# plus2_sram.net
KiCad netlist of a schematic drawn in EAGLE
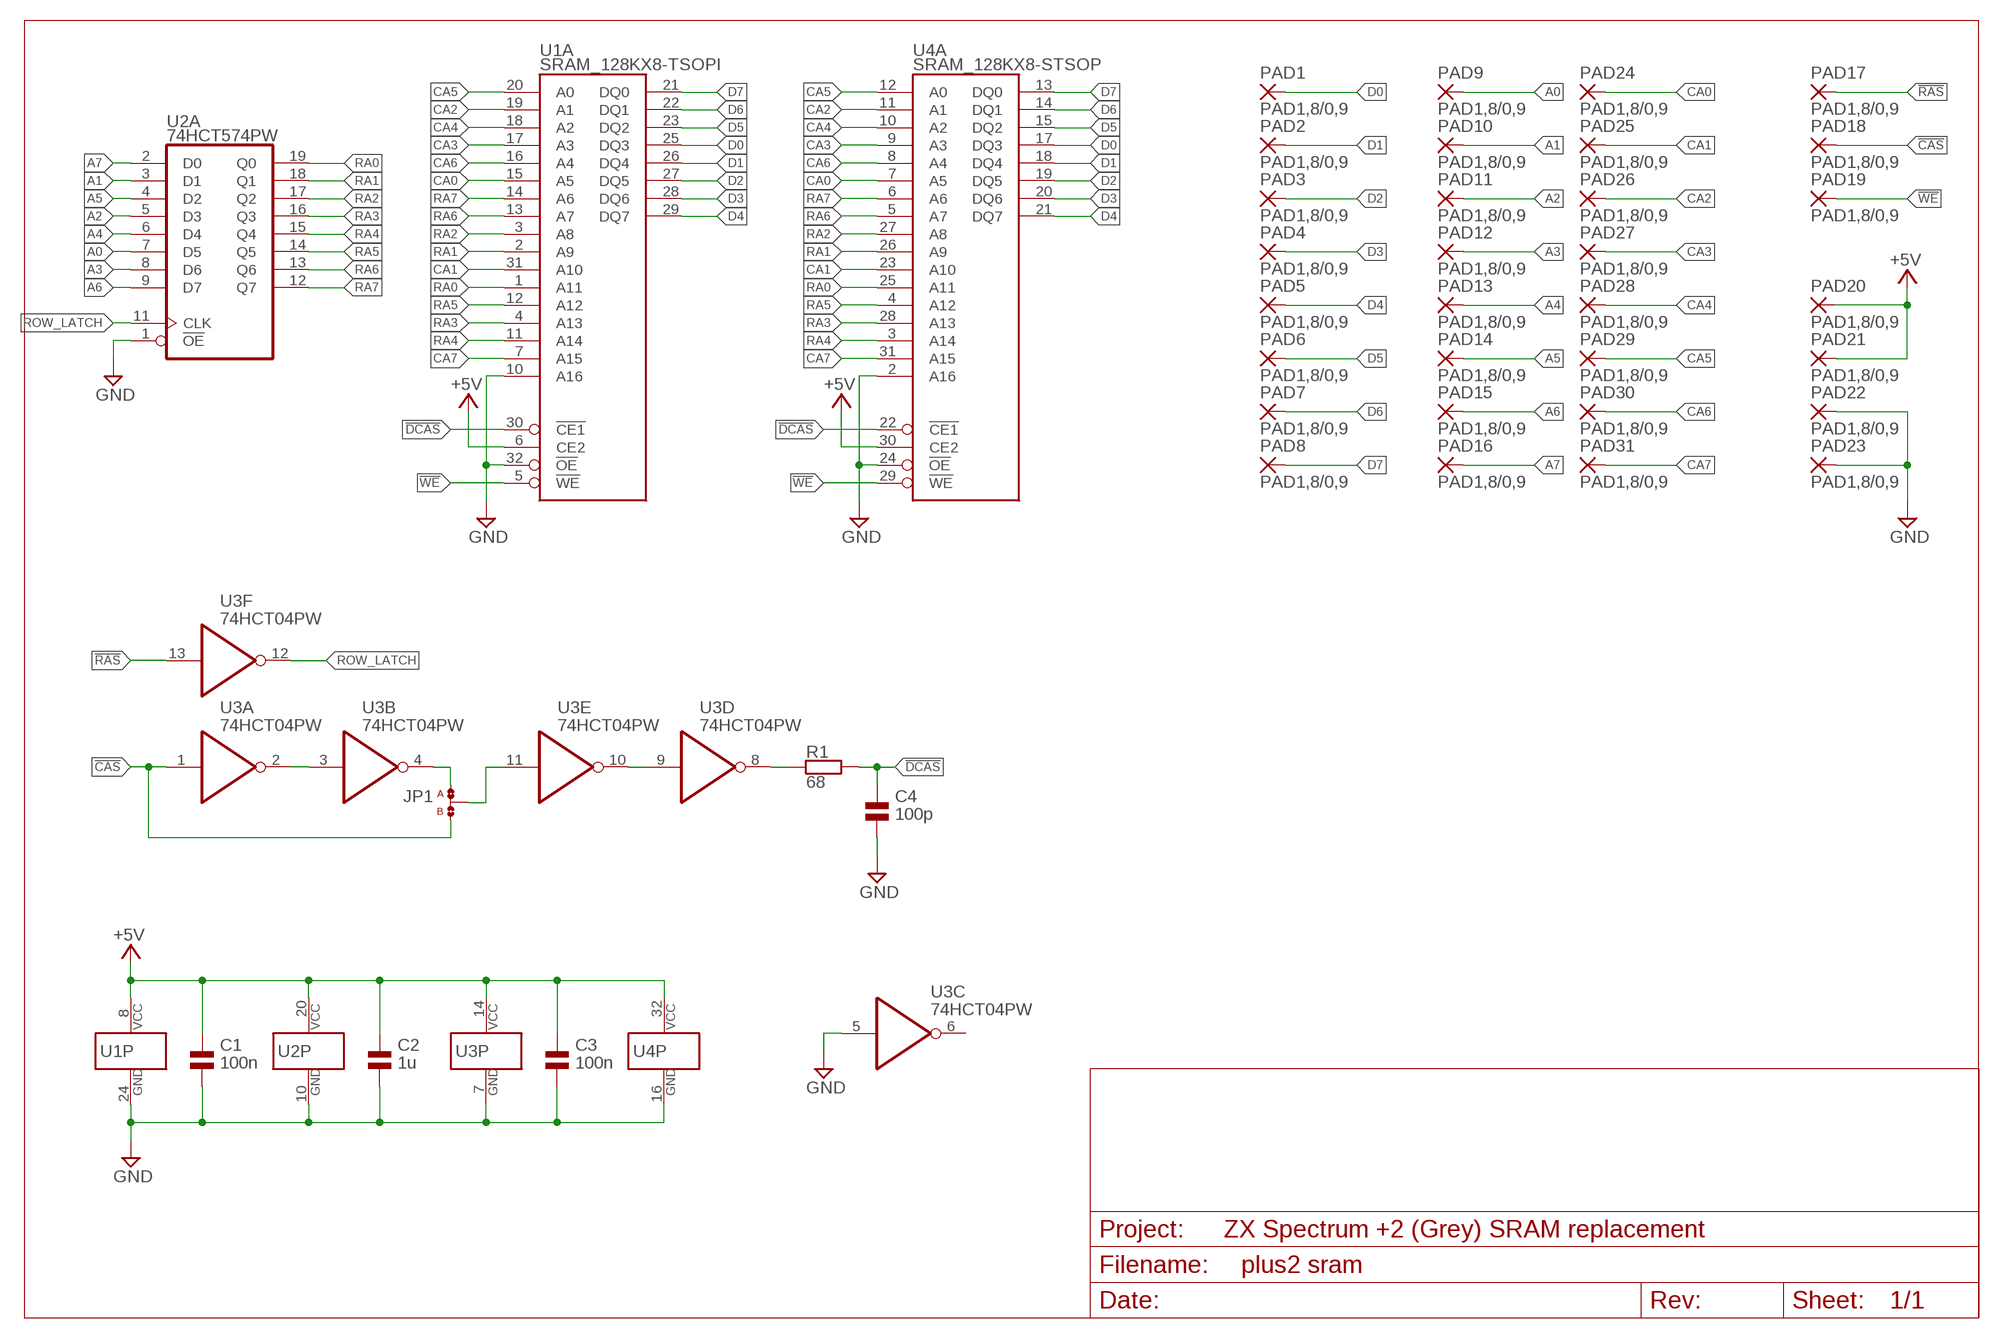
[diagram p0: schematic, sheet 1]

(export (version "E")
  (design (tool "Eeschema 10.0.6"))
  (components
    (comp (ref "C1")
      (value "100n")
      (footprint "eagle-import:0603")
      (libsource (lib "eagle-import") (part "CAP_NPOL0603-"))
    )
    (comp (ref "C2")
      (value "1u")
      (footprint "eagle-import:0603")
      (libsource (lib "eagle-import") (part "CAP_NPOL0603-"))
    )
    (comp (ref "C3")
      (value "100n")
      (footprint "eagle-import:0603")
      (libsource (lib "eagle-import") (part "CAP_NPOL0603-"))
    )
    (comp (ref "C4")
      (value "100p")
      (footprint "eagle-import:0603")
      (libsource (lib "eagle-import") (part "CAP_NPOL0603-"))
    )
    (comp (ref "JP1")
      (value "JMP-SMD-3W0805")
      (footprint "eagle-import:SJ-3P-0805")
      (libsource (lib "eagle-import") (part "JMP-SMD-3W0805"))
    )
    (comp (ref "PAD1")
      (value "PAD1,8/0,9")
      (footprint "eagle-import:1,8_0,9")
      (libsource (lib "eagle-import") (part "PAD1,8/0,9"))
    )
    (comp (ref "PAD2")
      (value "PAD1,8/0,9")
      (footprint "eagle-import:1,8_0,9")
      (libsource (lib "eagle-import") (part "PAD1,8/0,9"))
    )
    (comp (ref "PAD3")
      (value "PAD1,8/0,9")
      (footprint "eagle-import:1,8_0,9")
      (libsource (lib "eagle-import") (part "PAD1,8/0,9"))
    )
    (comp (ref "PAD4")
      (value "PAD1,8/0,9")
      (footprint "eagle-import:1,8_0,9")
      (libsource (lib "eagle-import") (part "PAD1,8/0,9"))
    )
    (comp (ref "PAD5")
      (value "PAD1,8/0,9")
      (footprint "eagle-import:1,8_0,9")
      (libsource (lib "eagle-import") (part "PAD1,8/0,9"))
    )
    (comp (ref "PAD6")
      (value "PAD1,8/0,9")
      (footprint "eagle-import:1,8_0,9")
      (libsource (lib "eagle-import") (part "PAD1,8/0,9"))
    )
    (comp (ref "PAD7")
      (value "PAD1,8/0,9")
      (footprint "eagle-import:1,8_0,9")
      (libsource (lib "eagle-import") (part "PAD1,8/0,9"))
    )
    (comp (ref "PAD8")
      (value "PAD1,8/0,9")
      (footprint "eagle-import:1,8_0,9")
      (libsource (lib "eagle-import") (part "PAD1,8/0,9"))
    )
    (comp (ref "PAD9")
      (value "PAD1,8/0,9")
      (footprint "eagle-import:1,8_0,9")
      (libsource (lib "eagle-import") (part "PAD1,8/0,9"))
    )
    (comp (ref "PAD10")
      (value "PAD1,8/0,9")
      (footprint "eagle-import:1,8_0,9")
      (libsource (lib "eagle-import") (part "PAD1,8/0,9"))
    )
    (comp (ref "PAD11")
      (value "PAD1,8/0,9")
      (footprint "eagle-import:1,8_0,9")
      (libsource (lib "eagle-import") (part "PAD1,8/0,9"))
    )
    (comp (ref "PAD12")
      (value "PAD1,8/0,9")
      (footprint "eagle-import:1,8_0,9")
      (libsource (lib "eagle-import") (part "PAD1,8/0,9"))
    )
    (comp (ref "PAD13")
      (value "PAD1,8/0,9")
      (footprint "eagle-import:1,8_0,9")
      (libsource (lib "eagle-import") (part "PAD1,8/0,9"))
    )
    (comp (ref "PAD14")
      (value "PAD1,8/0,9")
      (footprint "eagle-import:1,8_0,9")
      (libsource (lib "eagle-import") (part "PAD1,8/0,9"))
    )
    (comp (ref "PAD15")
      (value "PAD1,8/0,9")
      (footprint "eagle-import:1,8_0,9")
      (libsource (lib "eagle-import") (part "PAD1,8/0,9"))
    )
    (comp (ref "PAD16")
      (value "PAD1,8/0,9")
      (footprint "eagle-import:1,8_0,9")
      (libsource (lib "eagle-import") (part "PAD1,8/0,9"))
    )
    (comp (ref "PAD17")
      (value "PAD1,8/0,9")
      (footprint "eagle-import:1,8_0,9")
      (libsource (lib "eagle-import") (part "PAD1,8/0,9"))
    )
    (comp (ref "PAD18")
      (value "PAD1,8/0,9")
      (footprint "eagle-import:1,8_0,9")
      (libsource (lib "eagle-import") (part "PAD1,8/0,9"))
    )
    (comp (ref "PAD19")
      (value "PAD1,8/0,9")
      (footprint "eagle-import:1,8_0,9")
      (libsource (lib "eagle-import") (part "PAD1,8/0,9"))
    )
    (comp (ref "PAD20")
      (value "PAD1,8/0,9")
      (footprint "eagle-import:1,8_0,9")
      (libsource (lib "eagle-import") (part "PAD1,8/0,9"))
    )
    (comp (ref "PAD21")
      (value "PAD1,8/0,9")
      (footprint "eagle-import:1,8_0,9")
      (libsource (lib "eagle-import") (part "PAD1,8/0,9"))
    )
    (comp (ref "PAD22")
      (value "PAD1,8/0,9")
      (footprint "eagle-import:1,8_0,9")
      (libsource (lib "eagle-import") (part "PAD1,8/0,9"))
    )
    (comp (ref "PAD23")
      (value "PAD1,8/0,9")
      (footprint "eagle-import:1,8_0,9")
      (libsource (lib "eagle-import") (part "PAD1,8/0,9"))
    )
    (comp (ref "PAD24")
      (value "PAD1,8/0,9")
      (footprint "eagle-import:1,8_0,9")
      (libsource (lib "eagle-import") (part "PAD1,8/0,9"))
    )
    (comp (ref "PAD25")
      (value "PAD1,8/0,9")
      (footprint "eagle-import:1,8_0,9")
      (libsource (lib "eagle-import") (part "PAD1,8/0,9"))
    )
    (comp (ref "PAD26")
      (value "PAD1,8/0,9")
      (footprint "eagle-import:1,8_0,9")
      (libsource (lib "eagle-import") (part "PAD1,8/0,9"))
    )
    (comp (ref "PAD27")
      (value "PAD1,8/0,9")
      (footprint "eagle-import:1,8_0,9")
      (libsource (lib "eagle-import") (part "PAD1,8/0,9"))
    )
    (comp (ref "PAD28")
      (value "PAD1,8/0,9")
      (footprint "eagle-import:1,8_0,9")
      (libsource (lib "eagle-import") (part "PAD1,8/0,9"))
    )
    (comp (ref "PAD29")
      (value "PAD1,8/0,9")
      (footprint "eagle-import:1,8_0,9")
      (libsource (lib "eagle-import") (part "PAD1,8/0,9"))
    )
    (comp (ref "PAD30")
      (value "PAD1,8/0,9")
      (footprint "eagle-import:1,8_0,9")
      (libsource (lib "eagle-import") (part "PAD1,8/0,9"))
    )
    (comp (ref "PAD31")
      (value "PAD1,8/0,9")
      (footprint "eagle-import:1,8_0,9")
      (libsource (lib "eagle-import") (part "PAD1,8/0,9"))
    )
    (comp (ref "R1")
      (value "68")
      (footprint "eagle-import:0603")
      (libsource (lib "eagle-import") (part "RESSMD_0603-"))
    )
    (comp (ref "U1")
      (value "SRAM_128KX8-TSOPI")
      (footprint "eagle-import:TSOP-I-32")
      (libsource (lib "eagle-import") (part "SRAM_128KX8TSOPI-"))
    )
    (comp (ref "U2")
      (value "74HCT574PW")
      (footprint "eagle-import:TSSOP20")
      (libsource (lib "eagle-import") (part "74574PWHCT"))
    )
    (comp (ref "U3")
      (value "74HCT04PW")
      (footprint "eagle-import:TSSOP14")
      (libsource (lib "eagle-import") (part "7404PWHCT"))
    )
    (comp (ref "U4")
      (value "SRAM_128KX8-STSOP")
      (footprint "eagle-import:STSOP-32")
      (libsource (lib "eagle-import") (part "SRAM_128KX8STSOP-"))
    )
  )
  (nets
    (net (code "1") (name "+5V") (class "Default")
      (node (ref "C1") (pin "1") (pinfunction "1_1") (pintype "passive"))
      (node (ref "C2") (pin "1") (pinfunction "1_1") (pintype "passive"))
      (node (ref "C3") (pin "1") (pinfunction "1_1") (pintype "passive"))
      (node (ref "PAD20") (pin "1") (pinfunction "P_1") (pintype "passive"))
      (node (ref "PAD21") (pin "1") (pinfunction "P_1") (pintype "passive"))
      (node (ref "U1") (pin "6") (pinfunction "CE2_6") (pintype "input"))
      (node (ref "U1") (pin "8") (pinfunction "VCC_8") (pintype "power_in"))
      (node (ref "U2") (pin "20") (pinfunction "VCC_20") (pintype "power_in"))
      (node (ref "U3") (pin "14") (pinfunction "VCC_14") (pintype "power_in"))
      (node (ref "U4") (pin "30") (pinfunction "CE2_30") (pintype "input"))
      (node (ref "U4") (pin "32") (pinfunction "VCC_32") (pintype "power_in"))
    )
    (net (code "2") (name "/~{CAS}") (class "Default")
      (node (ref "JP1") (pin "B") (pinfunction "B_B") (pintype "passive"))
      (node (ref "PAD18") (pin "1") (pinfunction "P_1") (pintype "passive"))
      (node (ref "U3") (pin "1") (pinfunction "I_1") (pintype "input"))
    )
    (net (code "3") (name "/~{DCAS}") (class "Default")
      (node (ref "C4") (pin "1") (pinfunction "1_1") (pintype "passive"))
      (node (ref "R1") (pin "2") (pinfunction "2_2") (pintype "passive"))
      (node (ref "U1") (pin "30") (pinfunction "~{CE1}_30") (pintype "input"))
      (node (ref "U4") (pin "22") (pinfunction "~{CE1}_22") (pintype "input"))
    )
    (net (code "4") (name "/~{RAS}") (class "Default")
      (node (ref "PAD17") (pin "1") (pinfunction "P_1") (pintype "passive"))
      (node (ref "U3") (pin "13") (pinfunction "I_13") (pintype "input"))
    )
    (net (code "5") (name "/~{WE}") (class "Default")
      (node (ref "PAD19") (pin "1") (pinfunction "P_1") (pintype "passive"))
      (node (ref "U1") (pin "5") (pinfunction "~{WE}_5") (pintype "input"))
      (node (ref "U4") (pin "29") (pinfunction "~{WE}_29") (pintype "input"))
    )
    (net (code "6") (name "A0") (class "Default")
      (node (ref "PAD9") (pin "1") (pinfunction "P_1") (pintype "passive"))
      (node (ref "U2") (pin "7") (pinfunction "D5_7") (pintype "input"))
    )
    (net (code "7") (name "A1") (class "Default")
      (node (ref "PAD10") (pin "1") (pinfunction "P_1") (pintype "passive"))
      (node (ref "U2") (pin "3") (pinfunction "D1_3") (pintype "input"))
    )
    (net (code "8") (name "A2") (class "Default")
      (node (ref "PAD11") (pin "1") (pinfunction "P_1") (pintype "passive"))
      (node (ref "U2") (pin "5") (pinfunction "D3_5") (pintype "input"))
    )
    (net (code "9") (name "A3") (class "Default")
      (node (ref "PAD12") (pin "1") (pinfunction "P_1") (pintype "passive"))
      (node (ref "U2") (pin "8") (pinfunction "D6_8") (pintype "input"))
    )
    (net (code "10") (name "A4") (class "Default")
      (node (ref "PAD13") (pin "1") (pinfunction "P_1") (pintype "passive"))
      (node (ref "U2") (pin "6") (pinfunction "D4_6") (pintype "input"))
    )
    (net (code "11") (name "A5") (class "Default")
      (node (ref "PAD14") (pin "1") (pinfunction "P_1") (pintype "passive"))
      (node (ref "U2") (pin "4") (pinfunction "D2_4") (pintype "input"))
    )
    (net (code "12") (name "A6") (class "Default")
      (node (ref "PAD15") (pin "1") (pinfunction "P_1") (pintype "passive"))
      (node (ref "U2") (pin "9") (pinfunction "D7_9") (pintype "input"))
    )
    (net (code "13") (name "A7") (class "Default")
      (node (ref "PAD16") (pin "1") (pinfunction "P_1") (pintype "passive"))
      (node (ref "U2") (pin "2") (pinfunction "D0_2") (pintype "input"))
    )
    (net (code "14") (name "CA0") (class "Default")
      (node (ref "PAD24") (pin "1") (pinfunction "P_1") (pintype "passive"))
      (node (ref "U1") (pin "15") (pinfunction "A5_15") (pintype "input"))
      (node (ref "U4") (pin "7") (pinfunction "A5_7") (pintype "input"))
    )
    (net (code "15") (name "CA1") (class "Default")
      (node (ref "PAD25") (pin "1") (pinfunction "P_1") (pintype "passive"))
      (node (ref "U1") (pin "31") (pinfunction "A10_31") (pintype "input"))
      (node (ref "U4") (pin "23") (pinfunction "A10_23") (pintype "input"))
    )
    (net (code "16") (name "CA2") (class "Default")
      (node (ref "PAD26") (pin "1") (pinfunction "P_1") (pintype "passive"))
      (node (ref "U1") (pin "19") (pinfunction "A1_19") (pintype "input"))
      (node (ref "U4") (pin "11") (pinfunction "A1_11") (pintype "input"))
    )
    (net (code "17") (name "CA3") (class "Default")
      (node (ref "PAD27") (pin "1") (pinfunction "P_1") (pintype "passive"))
      (node (ref "U1") (pin "17") (pinfunction "A3_17") (pintype "input"))
      (node (ref "U4") (pin "9") (pinfunction "A3_9") (pintype "input"))
    )
    (net (code "18") (name "CA4") (class "Default")
      (node (ref "PAD28") (pin "1") (pinfunction "P_1") (pintype "passive"))
      (node (ref "U1") (pin "18") (pinfunction "A2_18") (pintype "input"))
      (node (ref "U4") (pin "10") (pinfunction "A2_10") (pintype "input"))
    )
    (net (code "19") (name "CA5") (class "Default")
      (node (ref "PAD29") (pin "1") (pinfunction "P_1") (pintype "passive"))
      (node (ref "U1") (pin "20") (pinfunction "A0_20") (pintype "input"))
      (node (ref "U4") (pin "12") (pinfunction "A0_12") (pintype "input"))
    )
    (net (code "20") (name "CA6") (class "Default")
      (node (ref "PAD30") (pin "1") (pinfunction "P_1") (pintype "passive"))
      (node (ref "U1") (pin "16") (pinfunction "A4_16") (pintype "input"))
      (node (ref "U4") (pin "8") (pinfunction "A4_8") (pintype "input"))
    )
    (net (code "21") (name "CA7") (class "Default")
      (node (ref "PAD31") (pin "1") (pinfunction "P_1") (pintype "passive"))
      (node (ref "U1") (pin "7") (pinfunction "A15_7") (pintype "input"))
      (node (ref "U4") (pin "31") (pinfunction "A15_31") (pintype "input"))
    )
    (net (code "22") (name "D0") (class "Default")
      (node (ref "PAD1") (pin "1") (pinfunction "P_1") (pintype "passive"))
      (node (ref "U1") (pin "25") (pinfunction "DQ3_25") (pintype "bidirectional"))
      (node (ref "U4") (pin "17") (pinfunction "DQ3_17") (pintype "bidirectional"))
    )
    (net (code "23") (name "D1") (class "Default")
      (node (ref "PAD2") (pin "1") (pinfunction "P_1") (pintype "passive"))
      (node (ref "U1") (pin "26") (pinfunction "DQ4_26") (pintype "bidirectional"))
      (node (ref "U4") (pin "18") (pinfunction "DQ4_18") (pintype "bidirectional"))
    )
    (net (code "24") (name "D2") (class "Default")
      (node (ref "PAD3") (pin "1") (pinfunction "P_1") (pintype "passive"))
      (node (ref "U1") (pin "27") (pinfunction "DQ5_27") (pintype "bidirectional"))
      (node (ref "U4") (pin "19") (pinfunction "DQ5_19") (pintype "bidirectional"))
    )
    (net (code "25") (name "D3") (class "Default")
      (node (ref "PAD4") (pin "1") (pinfunction "P_1") (pintype "passive"))
      (node (ref "U1") (pin "28") (pinfunction "DQ6_28") (pintype "bidirectional"))
      (node (ref "U4") (pin "20") (pinfunction "DQ6_20") (pintype "bidirectional"))
    )
    (net (code "26") (name "D4") (class "Default")
      (node (ref "PAD5") (pin "1") (pinfunction "P_1") (pintype "passive"))
      (node (ref "U1") (pin "29") (pinfunction "DQ7_29") (pintype "bidirectional"))
      (node (ref "U4") (pin "21") (pinfunction "DQ7_21") (pintype "bidirectional"))
    )
    (net (code "27") (name "D5") (class "Default")
      (node (ref "PAD6") (pin "1") (pinfunction "P_1") (pintype "passive"))
      (node (ref "U1") (pin "23") (pinfunction "DQ2_23") (pintype "bidirectional"))
      (node (ref "U4") (pin "15") (pinfunction "DQ2_15") (pintype "bidirectional"))
    )
    (net (code "28") (name "D6") (class "Default")
      (node (ref "PAD7") (pin "1") (pinfunction "P_1") (pintype "passive"))
      (node (ref "U1") (pin "22") (pinfunction "DQ1_22") (pintype "bidirectional"))
      (node (ref "U4") (pin "14") (pinfunction "DQ1_14") (pintype "bidirectional"))
    )
    (net (code "29") (name "D7") (class "Default")
      (node (ref "PAD8") (pin "1") (pinfunction "P_1") (pintype "passive"))
      (node (ref "U1") (pin "21") (pinfunction "DQ0_21") (pintype "bidirectional"))
      (node (ref "U4") (pin "13") (pinfunction "DQ0_13") (pintype "bidirectional"))
    )
    (net (code "30") (name "GND") (class "Default")
      (node (ref "C1") (pin "2") (pinfunction "2_2") (pintype "passive"))
      (node (ref "C2") (pin "2") (pinfunction "2_2") (pintype "passive"))
      (node (ref "C3") (pin "2") (pinfunction "2_2") (pintype "passive"))
      (node (ref "C4") (pin "2") (pinfunction "2_2") (pintype "passive"))
      (node (ref "PAD22") (pin "1") (pinfunction "P_1") (pintype "passive"))
      (node (ref "PAD23") (pin "1") (pinfunction "P_1") (pintype "passive"))
      (node (ref "U1") (pin "10") (pinfunction "A16_10") (pintype "input"))
      (node (ref "U1") (pin "24") (pinfunction "GND_24") (pintype "power_in"))
      (node (ref "U1") (pin "32") (pinfunction "~{OE}_32") (pintype "input"))
      (node (ref "U2") (pin "1") (pinfunction "~{OE}_1") (pintype "input"))
      (node (ref "U2") (pin "10") (pinfunction "GND_10") (pintype "power_in"))
      (node (ref "U3") (pin "5") (pinfunction "I_5") (pintype "input"))
      (node (ref "U3") (pin "7") (pinfunction "GND_7") (pintype "power_in"))
      (node (ref "U4") (pin "16") (pinfunction "GND_16") (pintype "power_in"))
      (node (ref "U4") (pin "2") (pinfunction "A16_2") (pintype "input"))
      (node (ref "U4") (pin "24") (pinfunction "~{OE}_24") (pintype "input"))
    )
    (net (code "31") (name "Net-(U3A-O)") (class "Default")
      (node (ref "U3") (pin "2") (pinfunction "O_2") (pintype "output"))
      (node (ref "U3") (pin "3") (pinfunction "I_3") (pintype "input"))
    )
    (net (code "32") (name "Net-(U3B-O)") (class "Default")
      (node (ref "JP1") (pin "A") (pinfunction "A_A") (pintype "passive"))
      (node (ref "U3") (pin "4") (pinfunction "O_4") (pintype "output"))
    )
    (net (code "33") (name "Net-(U3D-I)") (class "Default")
      (node (ref "U3") (pin "10") (pinfunction "O_10") (pintype "output"))
      (node (ref "U3") (pin "9") (pinfunction "I_9") (pintype "input"))
    )
    (net (code "34") (name "Net-(U3D-O)") (class "Default")
      (node (ref "R1") (pin "1") (pinfunction "1_1") (pintype "passive"))
      (node (ref "U3") (pin "8") (pinfunction "O_8") (pintype "output"))
    )
    (net (code "35") (name "Net-(U3E-I)") (class "Default")
      (node (ref "JP1") (pin "COM") (pinfunction "COM_COM") (pintype "passive"))
      (node (ref "U3") (pin "11") (pinfunction "I_11") (pintype "input"))
    )
    (net (code "36") (name "RA0") (class "Default")
      (node (ref "U1") (pin "1") (pinfunction "A11_1") (pintype "input"))
      (node (ref "U2") (pin "19") (pinfunction "Q0_19") (pintype "tri_state"))
      (node (ref "U4") (pin "25") (pinfunction "A11_25") (pintype "input"))
    )
    (net (code "37") (name "RA1") (class "Default")
      (node (ref "U1") (pin "2") (pinfunction "A9_2") (pintype "input"))
      (node (ref "U2") (pin "18") (pinfunction "Q1_18") (pintype "tri_state"))
      (node (ref "U4") (pin "26") (pinfunction "A9_26") (pintype "input"))
    )
    (net (code "38") (name "RA2") (class "Default")
      (node (ref "U1") (pin "3") (pinfunction "A8_3") (pintype "input"))
      (node (ref "U2") (pin "17") (pinfunction "Q2_17") (pintype "tri_state"))
      (node (ref "U4") (pin "27") (pinfunction "A8_27") (pintype "input"))
    )
    (net (code "39") (name "RA3") (class "Default")
      (node (ref "U1") (pin "4") (pinfunction "A13_4") (pintype "input"))
      (node (ref "U2") (pin "16") (pinfunction "Q3_16") (pintype "tri_state"))
      (node (ref "U4") (pin "28") (pinfunction "A13_28") (pintype "input"))
    )
    (net (code "40") (name "RA4") (class "Default")
      (node (ref "U1") (pin "11") (pinfunction "A14_11") (pintype "input"))
      (node (ref "U2") (pin "15") (pinfunction "Q4_15") (pintype "tri_state"))
      (node (ref "U4") (pin "3") (pinfunction "A14_3") (pintype "input"))
    )
    (net (code "41") (name "RA5") (class "Default")
      (node (ref "U1") (pin "12") (pinfunction "A12_12") (pintype "input"))
      (node (ref "U2") (pin "14") (pinfunction "Q5_14") (pintype "tri_state"))
      (node (ref "U4") (pin "4") (pinfunction "A12_4") (pintype "input"))
    )
    (net (code "42") (name "RA6") (class "Default")
      (node (ref "U1") (pin "13") (pinfunction "A7_13") (pintype "input"))
      (node (ref "U2") (pin "13") (pinfunction "Q6_13") (pintype "tri_state"))
      (node (ref "U4") (pin "5") (pinfunction "A7_5") (pintype "input"))
    )
    (net (code "43") (name "RA7") (class "Default")
      (node (ref "U1") (pin "14") (pinfunction "A6_14") (pintype "input"))
      (node (ref "U2") (pin "12") (pinfunction "Q7_12") (pintype "tri_state"))
      (node (ref "U4") (pin "6") (pinfunction "A6_6") (pintype "input"))
    )
    (net (code "44") (name "ROW_LATCH") (class "Default")
      (node (ref "U2") (pin "11") (pinfunction "CLK_11") (pintype "input"))
      (node (ref "U3") (pin "12") (pinfunction "O_12") (pintype "output"))
    )
    (net (code "45") (name "unconnected-(U3C-O-Pad6)") (class "Default")
      (node (ref "U3") (pin "6") (pinfunction "O_6") (pintype "output"))
    )
  )
)
